# BEP2_rev1_multiCB_RPM.net
KiCad netlist of a schematic drawn in EAGLE
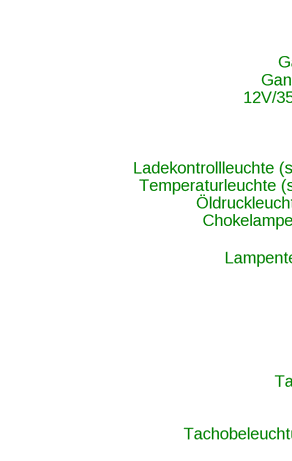
[diagram p0: schematic, sheet 1, part 1 of 2]
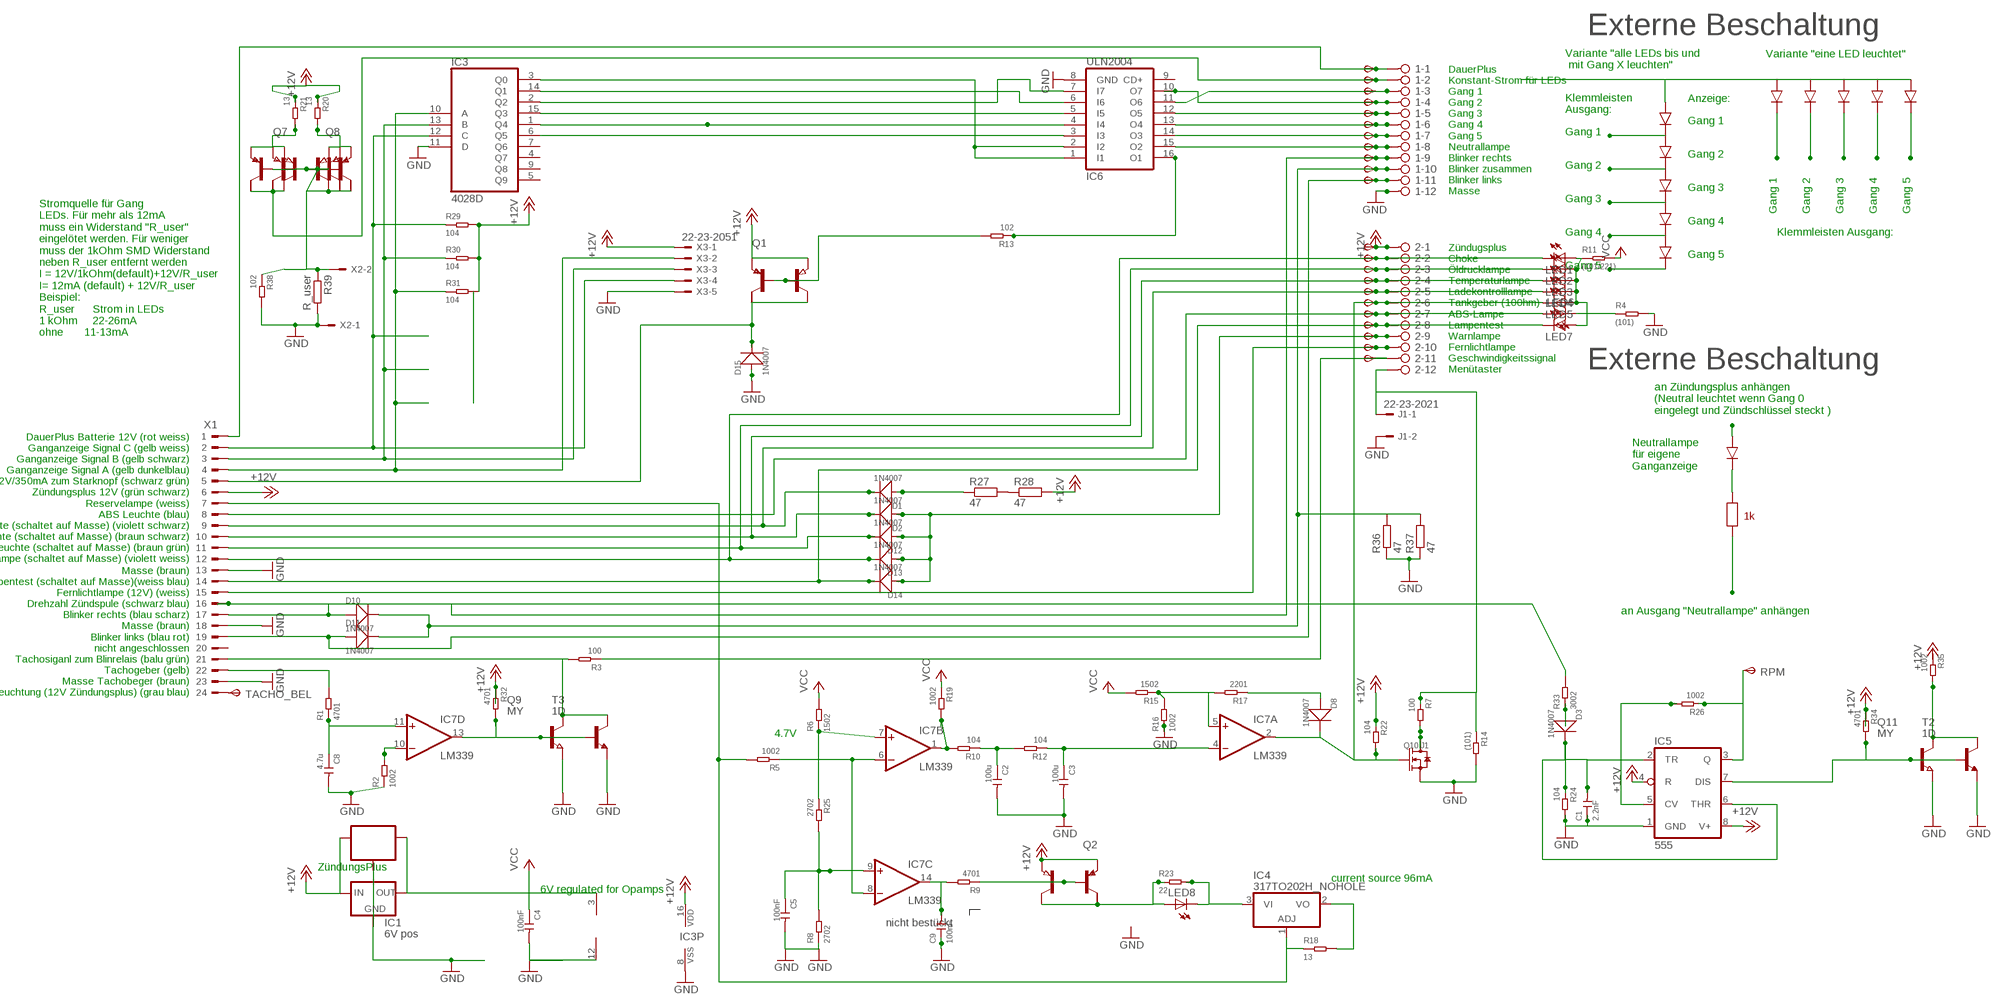
[diagram p1: schematic, sheet 1, part 2 of 2]

(export (version "E")
  (design (tool "Eeschema 10.0.6"))
  (components
    (comp (ref "1")
      (value "2081-1132")
      (footprint "eagle-import:12-PIN")
      (libsource (lib "eagle-import") (part "2081-1132"))
    )
    (comp (ref "2")
      (value "2081-1132")
      (footprint "eagle-import:12-PIN")
      (libsource (lib "eagle-import") (part "2081-1132"))
    )
    (comp (ref "C1")
      (value "2.2nF")
      (footprint "eagle-import:C0805")
      (fields (field (name "MPN") "CC0805KRX7R9BB104"))
      (libsource (lib "eagle-import") (part "CERAMIC-100NF-50V-10%-X7R(0805)"))
    )
    (comp (ref "C2")
      (value "100u")
      (footprint "eagle-import:C1206")
      (fields (field (name "MPN") "GRM31CR60J107ME39L"))
      (libsource (lib "eagle-import") (part "CERAMIC-100UF-6.3V-20%-X5R(1206)"))
    )
    (comp (ref "C3")
      (value "100u")
      (footprint "eagle-import:C1206")
      (fields (field (name "MPN") "GRM31CR60J107ME39L"))
      (libsource (lib "eagle-import") (part "CERAMIC-100UF-6.3V-20%-X5R(1206)"))
    )
    (comp (ref "C4")
      (value "100nF")
      (footprint "eagle-import:C0805")
      (fields (field (name "MPN") "CC0805KRX7R9BB104"))
      (libsource (lib "eagle-import") (part "CERAMIC-100NF-50V-10%-X7R(0805)"))
    )
    (comp (ref "C5")
      (value "100nF")
      (footprint "eagle-import:C0805")
      (fields (field (name "MPN") "CC0805KRX7R9BB104"))
      (libsource (lib "eagle-import") (part "CERAMIC-100NF-50V-10%-X7R(0805)"))
    )
    (comp (ref "C8")
      (value "4.7u")
      (footprint "eagle-import:C0805")
      (fields (field (name "MPN") "CC0805KKX5R8BB475"))
      (libsource (lib "eagle-import") (part "CERAMIC-4.7UF-25V-10%-X5R(0805)"))
    )
    (comp (ref "C9")
      (value "100nF")
      (footprint "eagle-import:C0805")
      (fields (field (name "MPN") "CC0805KRX7R9BB104"))
      (libsource (lib "eagle-import") (part "CERAMIC-100NF-50V-10%-X7R(0805)"))
    )
    (comp (ref "D1")
      (value "1N4007")
      (footprint "eagle-import:DO-214AC")
      (libsource (lib "eagle-import") (part "DIODE-GEN-PURPOSE-1KV-1A(DO-214AC)"))
    )
    (comp (ref "D2")
      (value "1N4007")
      (footprint "eagle-import:DO-214AC")
      (libsource (lib "eagle-import") (part "DIODE-GEN-PURPOSE-1KV-1A(DO-214AC)"))
    )
    (comp (ref "D3")
      (value "1N4007")
      (footprint "eagle-import:DO-214AC")
      (libsource (lib "eagle-import") (part "DIODE-GEN-PURPOSE-1KV-1A(DO-214AC)"))
    )
    (comp (ref "D8")
      (value "1N4007")
      (footprint "eagle-import:DO-214AC")
      (libsource (lib "eagle-import") (part "Seeed-Diode-2016_DIODE-GEN-PURPOSE-1KV-1A(DO-214AC)"))
    )
    (comp (ref "D10")
      (value "1N4007")
      (footprint "eagle-import:DO-214AC")
      (libsource (lib "eagle-import") (part "DIODE-GEN-PURPOSE-1KV-1A(DO-214AC)"))
    )
    (comp (ref "D11")
      (value "1N4007")
      (footprint "eagle-import:DO-214AC")
      (libsource (lib "eagle-import") (part "DIODE-GEN-PURPOSE-1KV-1A(DO-214AC)"))
    )
    (comp (ref "D12")
      (value "1N4007")
      (footprint "eagle-import:DO-214AC")
      (libsource (lib "eagle-import") (part "DIODE-GEN-PURPOSE-1KV-1A(DO-214AC)"))
    )
    (comp (ref "D13")
      (value "1N4007")
      (footprint "eagle-import:DO-214AC")
      (libsource (lib "eagle-import") (part "DIODE-GEN-PURPOSE-1KV-1A(DO-214AC)"))
    )
    (comp (ref "D14")
      (value "1N4007")
      (footprint "eagle-import:DO-214AC")
      (libsource (lib "eagle-import") (part "DIODE-GEN-PURPOSE-1KV-1A(DO-214AC)"))
    )
    (comp (ref "D15")
      (value "1N4007")
      (footprint "eagle-import:DO-214AC")
      (libsource (lib "eagle-import") (part "DIODE-GEN-PURPOSE-1KV-1A(DO-214AC)"))
    )
    (comp (ref "IC1")
      (value "6V pos")
      (footprint "eagle-import:78LXX")
      (libsource (lib "eagle-import") (part "v-reg_78LXX"))
    )
    (comp (ref "IC2")
      (value "78LXX-SOT89")
      (footprint "eagle-import:SOT89")
      (libsource (lib "eagle-import") (part "78LXX-SOT89"))
    )
    (comp (ref "IC3")
      (value "4028D")
      (footprint "eagle-import:SO16")
      (libsource (lib "eagle-import") (part "4028D"))
    )
    (comp (ref "IC4")
      (value "317TO202H_NOHOLE")
      (footprint "eagle-import:TO220H_NOHOLE")
      (libsource (lib "eagle-import") (part "317TO202H_NOHOLE"))
    )
    (comp (ref "IC5")
      (value "555")
      (footprint "eagle-import:SO08")
      (libsource (lib "eagle-import") (part "555DNE"))
    )
    (comp (ref "IC6")
      (value "ULN2004")
      (footprint "eagle-import:SO16")
      (libsource (lib "eagle-import") (part "ULN2004AD"))
    )
    (comp (ref "IC7")
      (value "LM339")
      (footprint "eagle-import:SO14")
      (libsource (lib "eagle-import") (part "LM339D"))
    )
    (comp (ref "J1")
      (value "22-23-2021")
      (footprint "eagle-import:22-23-2021")
      (fields (field (name "MF") "MOLEX"))
      (libsource (lib "eagle-import") (part "22-23-2021"))
    )
    (comp (ref "LED1")
      (value "LEDLD260")
      (footprint "eagle-import:LD260")
      (libsource (lib "eagle-import") (part "LEDLD260"))
    )
    (comp (ref "LED2")
      (value "LEDLD260")
      (footprint "eagle-import:LD260")
      (libsource (lib "eagle-import") (part "LEDLD260"))
    )
    (comp (ref "LED3")
      (value "LEDLD260")
      (footprint "eagle-import:LD260")
      (libsource (lib "eagle-import") (part "LEDLD260"))
    )
    (comp (ref "LED4")
      (value "LEDLD260")
      (footprint "eagle-import:LD260")
      (libsource (lib "eagle-import") (part "LEDLD260"))
    )
    (comp (ref "LED5")
      (value "LEDLD260")
      (footprint "eagle-import:LD260")
      (libsource (lib "eagle-import") (part "LEDLD260"))
    )
    (comp (ref "LED6")
      (value "LEDLD260")
      (footprint "eagle-import:LD260")
      (libsource (lib "eagle-import") (part "LEDLD260"))
    )
    (comp (ref "LED7")
      (value "LEDLD260")
      (footprint "eagle-import:LD260")
      (libsource (lib "eagle-import") (part "LEDLD260"))
    )
    (comp (ref "LED8")
      (value "LEDLD260")
      (footprint "eagle-import:LD260")
      (libsource (lib "eagle-import") (part "LEDLD260"))
    )
    (comp (ref "Q1")
      (value "PNP-TRANSISTOR_SOT89")
      (footprint "eagle-import:SOT89")
      (libsource (lib "eagle-import") (part "PNP-TRANSISTOR_SOT89"))
    )
    (comp (ref "Q2")
      (value "PNP-TRANSISTOR_SOT89")
      (footprint "eagle-import:SOT89")
      (libsource (lib "eagle-import") (part "PNP-TRANSISTOR_SOT89"))
    )
    (comp (ref "Q3")
      (value "AH-16")
      (footprint "eagle-import:SOT223")
      (libsource (lib "eagle-import") (part "BCP53T1"))
    )
    (comp (ref "Q4")
      (value "AH-16")
      (footprint "eagle-import:SOT223")
      (libsource (lib "eagle-import") (part "BCP53T1"))
    )
    (comp (ref "Q5")
      (value "(AH-16)")
      (footprint "eagle-import:SOT223")
      (libsource (lib "eagle-import") (part "BCP53T1"))
    )
    (comp (ref "Q6")
      (value "(AH-16)")
      (footprint "eagle-import:SOT223")
      (libsource (lib "eagle-import") (part "BCP53T1"))
    )
    (comp (ref "Q7")
      (value "PNP-TRANSISTOR_SOT89")
      (footprint "eagle-import:SOT89")
      (libsource (lib "eagle-import") (part "PNP-TRANSISTOR_SOT89"))
    )
    (comp (ref "Q8")
      (value "PNP-TRANSISTOR_SOT89")
      (footprint "eagle-import:SOT89")
      (libsource (lib "eagle-import") (part "PNP-TRANSISTOR_SOT89"))
    )
    (comp (ref "Q9")
      (value "MY")
      (footprint "eagle-import:SOT89")
      (libsource (lib "eagle-import") (part "NPN-TRANSISTOR_SOT89"))
    )
    (comp (ref "Q10")
      (value "J1")
      (footprint "eagle-import:SOT-23")
      (fields (field (name "MPN") "BSS138W-7-F"))
      (libsource (lib "eagle-import") (part "SMD-MOSFET-N-CH-50V-200MA-BSS138W-7-F(SOT-23)"))
    )
    (comp (ref "Q11")
      (value "MY")
      (footprint "eagle-import:SOT89")
      (libsource (lib "eagle-import") (part "NPN-TRANSISTOR_SOT89"))
    )
    (comp (ref "R1")
      (value "4701")
      (footprint "eagle-import:R0805")
      (fields (field (name "MPN") "RC0805JR-074K7L"))
      (libsource (lib "eagle-import") (part "SMD-RES-4.7K-5%-1/8W(0805)"))
    )
    (comp (ref "R2")
      (value "1002")
      (footprint "eagle-import:R0805")
      (fields (field (name "MPN") "RC0805FR-0710KL"))
      (libsource (lib "eagle-import") (part "SMD-RES-10K-1%-1/8W(0805)"))
    )
    (comp (ref "R3")
      (value "100")
      (footprint "eagle-import:R0805")
      (fields (field (name "MPN") "RC0805JR-07220RL"))
      (libsource (lib "eagle-import") (part "SMD-RES-220R-5%-1/8W(0805)"))
    )
    (comp (ref "R4")
      (value "(101)")
      (footprint "eagle-import:R0805")
      (fields (field (name "MPN") "RC0805JR-07100RL"))
      (libsource (lib "eagle-import") (part "SMD-RES-100R-5%-1/8W(0805)"))
    )
    (comp (ref "R5")
      (value "1002")
      (footprint "eagle-import:R0805")
      (fields (field (name "MPN") "RC0805FR-0710KL"))
      (libsource (lib "eagle-import") (part "SMD-RES-10K-1%-1/8W(0805)"))
    )
    (comp (ref "R6")
      (value "1502")
      (footprint "eagle-import:R0805")
      (fields (field (name "MPN") "RC0805FR-0710KL"))
      (libsource (lib "eagle-import") (part "SMD-RES-10K-1%-1/8W(0805)"))
    )
    (comp (ref "R7")
      (value "100")
      (footprint "eagle-import:R0805")
      (fields (field (name "MPN") "RC0805JR-072K2L"))
      (libsource (lib "eagle-import") (part "SMD-RES-2.2K-5%-1/8W(0805)"))
    )
    (comp (ref "R8")
      (value "2702")
      (footprint "eagle-import:R0805")
      (fields (field (name "MPN") "RC0805JR-074K7L"))
      (libsource (lib "eagle-import") (part "SMD-RES-4.7K-5%-1/8W(0805)"))
    )
    (comp (ref "R9")
      (value "4701")
      (footprint "eagle-import:R0805")
      (fields (field (name "MPN") "RC0805JR-074K7L"))
      (libsource (lib "eagle-import") (part "SMD-RES-4.7K-5%-1/8W(0805)"))
    )
    (comp (ref "R10")
      (value "104")
      (footprint "eagle-import:R0805")
      (fields (field (name "MPN") "RC0805FR-0710KL"))
      (libsource (lib "eagle-import") (part "SMD-RES-10K-1%-1/8W(0805)"))
    )
    (comp (ref "R11")
      (value "(101/221)")
      (footprint "eagle-import:R0805")
      (fields (field (name "MPN") "RC0805JR-07100RL"))
      (libsource (lib "eagle-import") (part "SMD-RES-100R-5%-1/8W(0805)"))
    )
    (comp (ref "R12")
      (value "104")
      (footprint "eagle-import:R0805")
      (fields (field (name "MPN") "RC0805FR-0710KL"))
      (libsource (lib "eagle-import") (part "SMD-RES-10K-1%-1/8W(0805)"))
    )
    (comp (ref "R13")
      (value "102")
      (footprint "eagle-import:R0805")
      (fields (field (name "MPN") "RC0805JR-071KL"))
      (libsource (lib "eagle-import") (part "SMD-RES-1K-5%-1/8W(0805)"))
    )
    (comp (ref "R14")
      (value "(101)")
      (footprint "eagle-import:R0805")
      (fields (field (name "MPN") "RC0805JR-072K2L"))
      (libsource (lib "eagle-import") (part "SMD-RES-2.2K-5%-1/8W(0805)"))
    )
    (comp (ref "R15")
      (value "1502")
      (footprint "eagle-import:R0805")
      (fields (field (name "MPN") "RC0805FR-0710KL"))
      (libsource (lib "eagle-import") (part "SMD-RES-10K-1%-1/8W(0805)"))
    )
    (comp (ref "R16")
      (value "1002")
      (footprint "eagle-import:R0805")
      (fields (field (name "MPN") "RC0805FR-0710KL"))
      (libsource (lib "eagle-import") (part "SMD-RES-10K-1%-1/8W(0805)"))
    )
    (comp (ref "R17")
      (value "2201")
      (footprint "eagle-import:R0805")
      (fields (field (name "MPN") "RC0805JR-072K2L"))
      (libsource (lib "eagle-import") (part "SMD-RES-2.2K-5%-1/8W(0805)"))
    )
    (comp (ref "R18")
      (value "13")
      (footprint "eagle-import:R1206")
      (fields (field (name "MPN") "RC1206JR-0713RL"))
      (libsource (lib "eagle-import") (part "SMD-RES-13R-5%-1/4W(1206)"))
    )
    (comp (ref "R19")
      (value "1002")
      (footprint "eagle-import:R0805")
      (fields (field (name "MPN") "RC0805FR-0710KL"))
      (libsource (lib "eagle-import") (part "SMD-RES-10K-1%-1/8W(0805)"))
    )
    (comp (ref "R20")
      (value "13")
      (footprint "eagle-import:R1206")
      (fields (field (name "MPN") "RC1206JR-0713RL"))
      (libsource (lib "eagle-import") (part "SMD-RES-13R-5%-1/4W(1206)"))
    )
    (comp (ref "R21")
      (value "13")
      (footprint "eagle-import:R1206")
      (fields (field (name "MPN") "RC1206JR-0713RL"))
      (libsource (lib "eagle-import") (part "SMD-RES-13R-5%-1/4W(1206)"))
    )
    (comp (ref "R22")
      (value "104")
      (footprint "eagle-import:R0805")
      (fields (field (name "MPN") "RC0805FR-0710KL"))
      (libsource (lib "eagle-import") (part "SMD-RES-10K-1%-1/8W(0805)"))
    )
    (comp (ref "R23")
      (value "22")
      (footprint "eagle-import:R1206")
      (fields (field (name "MPN") "RC1206JR-0713RL"))
      (libsource (lib "eagle-import") (part "SMD-RES-13R-5%-1/4W(1206)"))
    )
    (comp (ref "R24")
      (value "104")
      (footprint "eagle-import:R0805")
      (fields (field (name "MPN") "RC0805FR-0710KL"))
      (libsource (lib "eagle-import") (part "SMD-RES-10K-1%-1/8W(0805)"))
    )
    (comp (ref "R25")
      (value "2702")
      (footprint "eagle-import:R0805")
      (fields (field (name "MPN") "RC0805JR-074K7L"))
      (libsource (lib "eagle-import") (part "SMD-RES-4.7K-5%-1/8W(0805)"))
    )
    (comp (ref "R26")
      (value "1002")
      (footprint "eagle-import:R0805")
      (fields (field (name "MPN") "RC0805FR-0710KL"))
      (libsource (lib "eagle-import") (part "SMD-RES-10K-1%-1/8W(0805)"))
    )
    (comp (ref "R27")
      (value "47")
      (footprint "eagle-import:V235_17_1MM")
      (libsource (lib "eagle-import") (part "R-EU_V235/17_1MM"))
    )
    (comp (ref "R28")
      (value "47")
      (footprint "eagle-import:V235_17_1MM")
      (libsource (lib "eagle-import") (part "R-EU_V235/17_1MM"))
    )
    (comp (ref "R29")
      (value "104")
      (footprint "eagle-import:R0805")
      (fields (field (name "MPN") "RC0805FR-0710KL"))
      (libsource (lib "eagle-import") (part "SMD-RES-10K-1%-1/8W(0805)"))
    )
    (comp (ref "R30")
      (value "104")
      (footprint "eagle-import:R0805")
      (fields (field (name "MPN") "RC0805FR-0710KL"))
      (libsource (lib "eagle-import") (part "SMD-RES-10K-1%-1/8W(0805)"))
    )
    (comp (ref "R31")
      (value "104")
      (footprint "eagle-import:R0805")
      (fields (field (name "MPN") "RC0805FR-0710KL"))
      (libsource (lib "eagle-import") (part "SMD-RES-10K-1%-1/8W(0805)"))
    )
    (comp (ref "R32")
      (value "4701")
      (footprint "eagle-import:R0805")
      (fields (field (name "MPN") "RC0805JR-074K7L"))
      (libsource (lib "eagle-import") (part "SMD-RES-4.7K-5%-1/8W(0805)"))
    )
    (comp (ref "R33")
      (value "3002")
      (footprint "eagle-import:R0805")
      (fields (field (name "MPN") "RC0805FR-0710KL"))
      (libsource (lib "eagle-import") (part "SMD-RES-10K-1%-1/8W(0805)"))
    )
    (comp (ref "R34")
      (value "4701")
      (footprint "eagle-import:R0805")
      (fields (field (name "MPN") "RC0805JR-074K7L"))
      (libsource (lib "eagle-import") (part "SMD-RES-4.7K-5%-1/8W(0805)"))
    )
    (comp (ref "R35")
      (value "1002")
      (footprint "eagle-import:R0805")
      (fields (field (name "MPN") "RC0805JR-074K7L"))
      (libsource (lib "eagle-import") (part "SMD-RES-4.7K-5%-1/8W(0805)"))
    )
    (comp (ref "R36")
      (value "47")
      (footprint "eagle-import:V235_17_1MM")
      (libsource (lib "eagle-import") (part "R-EU_V235/17_1MM"))
    )
    (comp (ref "R37")
      (value "47")
      (footprint "eagle-import:V235_17_1MM")
      (libsource (lib "eagle-import") (part "R-EU_V235/17_1MM"))
    )
    (comp (ref "R38")
      (value "102")
      (footprint "eagle-import:R0805")
      (fields (field (name "MPN") "RC0805JR-071KL"))
      (libsource (lib "eagle-import") (part "SMD-RES-1K-5%-1/8W(0805)"))
    )
    (comp (ref "R39")
      (value "R_user")
      (footprint "eagle-import:R0805")
      (libsource (lib "eagle-import") (part "R-EU_R0805"))
    )
    (comp (ref "RPM")
      (value "TPSP1_1MM")
      (footprint "eagle-import:P1_1.0MM")
      (libsource (lib "eagle-import") (part "TPSP1_1MM"))
    )
    (comp (ref "T1")
      (value "PNP2SM8")
      (footprint "eagle-import:SM8")
      (libsource (lib "eagle-import") (part "PNP2SM8"))
    )
    (comp (ref "T2")
      (value "1D")
      (footprint "eagle-import:SOT23-BEC")
      (libsource (lib "eagle-import") (part "-NPN-SOT23-BECMMBTA42LT1"))
    )
    (comp (ref "T3")
      (value "1D")
      (footprint "eagle-import:SOT23-BEC")
      (libsource (lib "eagle-import") (part "-NPN-SOT23-BECMMBTA42LT1"))
    )
    (comp (ref "TACHO_BEL")
      (value "TPSP1_1MM")
      (footprint "eagle-import:P1_1.0MM")
      (libsource (lib "eagle-import") (part "TPSP1_1MM"))
    )
    (comp (ref "TP1")
      (value "TPSB1.8")
      (footprint "eagle-import:B1.8")
      (libsource (lib "eagle-import") (part "TPSB1.8"))
    )
    (comp (ref "TP2")
      (value "TPSB1.8")
      (footprint "eagle-import:B1.8")
      (libsource (lib "eagle-import") (part "TPSB1.8"))
    )
    (comp (ref "TP3")
      (value "TPSB1.8")
      (footprint "eagle-import:B1.8")
      (libsource (lib "eagle-import") (part "TPSB1.8"))
    )
    (comp (ref "TP4")
      (value "TPSB1.8")
      (footprint "eagle-import:B1.8")
      (libsource (lib "eagle-import") (part "TPSB1.8"))
    )
    (comp (ref "TP5")
      (value "TPSB1.8")
      (footprint "eagle-import:B1.8")
      (libsource (lib "eagle-import") (part "TPSB1.8"))
    )
    (comp (ref "TP6")
      (value "TPSB1.8")
      (footprint "eagle-import:B1.8")
      (libsource (lib "eagle-import") (part "TPSB1.8"))
    )
    (comp (ref "TP7")
      (value "TPSB1.8")
      (footprint "eagle-import:B1.8")
      (libsource (lib "eagle-import") (part "TPSB1.8"))
    )
    (comp (ref "TP8")
      (value "TPSB1.8")
      (footprint "eagle-import:B1.8")
      (libsource (lib "eagle-import") (part "TPSB1.8"))
    )
    (comp (ref "TP9")
      (value "TPSB1.8")
      (footprint "eagle-import:B1.8")
      (libsource (lib "eagle-import") (part "TPSB1.8"))
    )
    (comp (ref "TP10")
      (value "TPSB1.8")
      (footprint "eagle-import:B1.8")
      (libsource (lib "eagle-import") (part "TPSB1.8"))
    )
    (comp (ref "TP11")
      (value "TPSB1.8")
      (footprint "eagle-import:B1.8")
      (libsource (lib "eagle-import") (part "TPSB1.8"))
    )
    (comp (ref "TP12")
      (value "TPSB1.8")
      (footprint "eagle-import:B1.8")
      (libsource (lib "eagle-import") (part "TPSB1.8"))
    )
    (comp (ref "TP16")
      (value "TPSB1.8")
      (footprint "eagle-import:B1.8")
      (libsource (lib "eagle-import") (part "TPSB1.8"))
    )
    (comp (ref "TP17")
      (value "TPSB1.8")
      (footprint "eagle-import:B1.8")
      (libsource (lib "eagle-import") (part "TPSB1.8"))
    )
    (comp (ref "TP18")
      (value "TPSB1.8")
      (footprint "eagle-import:B1.8")
      (libsource (lib "eagle-import") (part "TPSB1.8"))
    )
    (comp (ref "TP19")
      (value "TPSB1.8")
      (footprint "eagle-import:B1.8")
      (libsource (lib "eagle-import") (part "TPSB1.8"))
    )
    (comp (ref "TP21")
      (value "TPSB1.8")
      (footprint "eagle-import:B1.8")
      (libsource (lib "eagle-import") (part "TPSB1.8"))
    )
    (comp (ref "TP22")
      (value "TPSB1.8")
      (footprint "eagle-import:B1.8")
      (libsource (lib "eagle-import") (part "TPSB1.8"))
    )
    (comp (ref "TP23")
      (value "TPSB1.8")
      (footprint "eagle-import:B1.8")
      (libsource (lib "eagle-import") (part "TPSB1.8"))
    )
    (comp (ref "TP24")
      (value "TPSB1,27")
      (footprint "eagle-import:B1,27")
      (libsource (lib "eagle-import") (part "TPSB1,27"))
    )
    (comp (ref "TP25")
      (value "TPSB1.8")
      (footprint "eagle-import:B1.8")
      (libsource (lib "eagle-import") (part "TPSB1.8"))
    )
    (comp (ref "TP26")
      (value "TPSB1.8")
      (footprint "eagle-import:B1.8")
      (libsource (lib "eagle-import") (part "TPSB1.8"))
    )
    (comp (ref "X1")
      (value "CON_BMWV2")
      (footprint "eagle-import:24-PIN_V2")
      (libsource (lib "eagle-import") (part "CON_BMWV2"))
    )
    (comp (ref "X2")
      (value "22-23-2021")
      (footprint "eagle-import:22-23-2021")
      (fields (field (name "MF") "MOLEX"))
      (libsource (lib "eagle-import") (part "22-23-2021"))
    )
    (comp (ref "X3")
      (value "22-23-2051")
      (footprint "eagle-import:22-23-2051")
      (fields (field (name "MF") "MOLEX"))
      (libsource (lib "eagle-import") (part "22-23-2051"))
    )
  )
  (nets
    (net (code "1") (name "+12V") (class "Default")
      (node (ref "2") (pin "1") (pinfunction "KL_1") (pintype "passive"))
      (node (ref "IC1") (pin "IN") (pinfunction "IN_IN") (pintype "input"))
      (node (ref "IC2") (pin "3") (pinfunction "IN_3") (pintype "input"))
      (node (ref "IC3") (pin "16") (pinfunction "VDD_16") (pintype "power_in"))
      (node (ref "IC5") (pin "4") (pinfunction "R_4") (pintype "input"))
      (node (ref "IC5") (pin "8") (pinfunction "V+_8") (pintype "power_in"))
      (node (ref "Q1") (pin "3") (pinfunction "E_3") (pintype "passive"))
      (node (ref "Q2") (pin "3") (pinfunction "E_3") (pintype "passive"))
      (node (ref "Q3") (pin "3") (pinfunction "E_3") (pintype "passive"))
      (node (ref "Q4") (pin "3") (pinfunction "E_3") (pintype "passive"))
      (node (ref "R20") (pin "1") (pinfunction "1_1") (pintype "passive"))
      (node (ref "R21") (pin "1") (pinfunction "1_1") (pintype "passive"))
      (node (ref "R22") (pin "1") (pinfunction "1_1") (pintype "passive"))
      (node (ref "R28") (pin "2") (pinfunction "2_2") (pintype "passive"))
      (node (ref "R29") (pin "2") (pinfunction "2_2") (pintype "passive"))
      (node (ref "R30") (pin "2") (pinfunction "2_2") (pintype "passive"))
      (node (ref "R31") (pin "2") (pinfunction "2_2") (pintype "passive"))
      (node (ref "R32") (pin "1") (pinfunction "1_1") (pintype "passive"))
      (node (ref "R34") (pin "1") (pinfunction "1_1") (pintype "passive"))
      (node (ref "TP12") (pin "TP") (pinfunction "PP_TP") (pintype "input"))
      (node (ref "X1") (pin "6") (pinfunction "6_6") (pintype "passive"))
      (node (ref "X3") (pin "1") (pinfunction "S_1") (pintype "passive"))
    )
    (net (code "2") (name "GND") (class "Default")
      (node (ref "1") (pin "12") (pinfunction "KL_12") (pintype "passive"))
      (node (ref "C1") (pin "1") (pinfunction "1_1") (pintype "passive"))
      (node (ref "C2") (pin "2") (pinfunction "2_2") (pintype "passive"))
      (node (ref "C3") (pin "2") (pinfunction "2_2") (pintype "passive"))
      (node (ref "C4") (pin "2") (pinfunction "2_2") (pintype "passive"))
      (node (ref "C5") (pin "2") (pinfunction "2_2") (pintype "passive"))
      (node (ref "C8") (pin "2") (pinfunction "2_2") (pintype "passive"))
      (node (ref "C9") (pin "1") (pinfunction "1_1") (pintype "passive"))
      (node (ref "D15") (pin "1") (pinfunction "+_1") (pintype "passive"))
      (node (ref "IC1") (pin "GND") (pinfunction "GND_GND") (pintype "input"))
      (node (ref "IC2") (pin "2") (pinfunction "GND_2") (pintype "input"))
      (node (ref "IC2") (pin "4") (pinfunction "GND_4") (pintype "input"))
      (node (ref "IC3") (pin "11") (pinfunction "D_11") (pintype "input"))
      (node (ref "IC3") (pin "8") (pinfunction "VSS_8") (pintype "power_in"))
      (node (ref "IC5") (pin "1") (pinfunction "GND_1") (pintype "power_in"))
      (node (ref "IC6") (pin "8") (pinfunction "GND_8") (pintype "power_in"))
      (node (ref "IC7") (pin "12") (pinfunction "GND_12") (pintype "power_in"))
      (node (ref "J1") (pin "2") (pinfunction "S_2") (pintype "passive"))
      (node (ref "Q10") (pin "2") (pinfunction "S_2") (pintype "passive"))
      (node (ref "Q11") (pin "3") (pinfunction "E_3") (pintype "passive"))
      (node (ref "Q9") (pin "3") (pinfunction "E_3") (pintype "passive"))
      (node (ref "R14") (pin "2") (pinfunction "2_2") (pintype "passive"))
      (node (ref "R16") (pin "1") (pinfunction "1_1") (pintype "passive"))
      (node (ref "R2") (pin "1") (pinfunction "1_1") (pintype "passive"))
      (node (ref "R24") (pin "2") (pinfunction "2_2") (pintype "passive"))
      (node (ref "R36") (pin "1") (pinfunction "1_1") (pintype "passive"))
      (node (ref "R37") (pin "1") (pinfunction "1_1") (pintype "passive"))
      (node (ref "R38") (pin "2") (pinfunction "2_2") (pintype "passive"))
      (node (ref "R39") (pin "2") (pinfunction "2_2") (pintype "passive"))
      (node (ref "R4") (pin "2") (pinfunction "2_2") (pintype "passive"))
      (node (ref "R8") (pin "1") (pinfunction "1_1") (pintype "passive"))
      (node (ref "T2") (pin "E") (pinfunction "E_E") (pintype "passive"))
      (node (ref "T3") (pin "E") (pinfunction "E_E") (pintype "passive"))
      (node (ref "X1") (pin "13") (pinfunction "13_13") (pintype "passive"))
      (node (ref "X1") (pin "18") (pinfunction "18_18") (pintype "passive"))
      (node (ref "X1") (pin "23") (pinfunction "23_23") (pintype "passive"))
      (node (ref "X2") (pin "1") (pinfunction "S_1") (pintype "passive"))
      (node (ref "X3") (pin "5") (pinfunction "S_5") (pintype "passive"))
    )
    (net (code "3") (name "Net-(1A-KL)") (class "Default")
      (node (ref "1") (pin "1") (pinfunction "KL_1") (pintype "passive"))
      (node (ref "TP1") (pin "TP") (pinfunction "PP_TP") (pintype "input"))
      (node (ref "X1") (pin "1") (pinfunction "1_1") (pintype "passive"))
    )
    (net (code "4") (name "Net-(1B-KL)") (class "Default")
      (node (ref "1") (pin "10") (pinfunction "KL_10") (pintype "passive"))
      (node (ref "D10") (pin "2") (pinfunction "-_2") (pintype "passive"))
      (node (ref "D11") (pin "2") (pinfunction "-_2") (pintype "passive"))
      (node (ref "R36") (pin "2") (pinfunction "2_2") (pintype "passive"))
      (node (ref "R37") (pin "2") (pinfunction "2_2") (pintype "passive"))
      (node (ref "TP10") (pin "TP") (pinfunction "PP_TP") (pintype "input"))
    )
    (net (code "5") (name "Net-(1C-KL)") (class "Default")
      (node (ref "1") (pin "11") (pinfunction "KL_11") (pintype "passive"))
      (node (ref "D11") (pin "1") (pinfunction "+_1") (pintype "passive"))
      (node (ref "TP11") (pin "TP") (pinfunction "PP_TP") (pintype "input"))
      (node (ref "X1") (pin "19") (pinfunction "19_19") (pintype "passive"))
    )
    (net (code "6") (name "Net-(1E-KL)") (class "Default")
      (node (ref "1") (pin "2") (pinfunction "KL_2") (pintype "passive"))
      (node (ref "Q5") (pin "2") (pinfunction "C_2") (pintype "passive"))
      (node (ref "Q8") (pin "2") (pinfunction "C_2") (pintype "passive"))
      (node (ref "T1") (pin "8") (pinfunction "C1_8") (pintype "passive"))
      (node (ref "TP2") (pin "TP") (pinfunction "PP_TP") (pintype "input"))
    )
    (net (code "7") (name "Net-(1F-KL)") (class "Default")
      (node (ref "1") (pin "3") (pinfunction "KL_3") (pintype "passive"))
      (node (ref "IC6") (pin "11") (pinfunction "O6_11") (pintype "open_collector"))
      (node (ref "TP3") (pin "TP") (pinfunction "PP_TP") (pintype "input"))
    )
    (net (code "8") (name "Net-(1G-KL)") (class "Default")
      (node (ref "1") (pin "4") (pinfunction "KL_4") (pintype "passive"))
      (node (ref "IC6") (pin "10") (pinfunction "O7_10") (pintype "open_collector"))
      (node (ref "TP4") (pin "TP") (pinfunction "PP_TP") (pintype "input"))
    )
    (net (code "9") (name "Net-(1H-KL)") (class "Default")
      (node (ref "1") (pin "5") (pinfunction "KL_5") (pintype "passive"))
      (node (ref "IC6") (pin "12") (pinfunction "O5_12") (pintype "open_collector"))
      (node (ref "TP5") (pin "TP") (pinfunction "PP_TP") (pintype "input"))
    )
    (net (code "10") (name "Net-(1I-KL)") (class "Default")
      (node (ref "1") (pin "6") (pinfunction "KL_6") (pintype "passive"))
      (node (ref "IC6") (pin "13") (pinfunction "O4_13") (pintype "open_collector"))
      (node (ref "TP6") (pin "TP") (pinfunction "PP_TP") (pintype "input"))
    )
    (net (code "11") (name "Net-(1J-KL)") (class "Default")
      (node (ref "1") (pin "7") (pinfunction "KL_7") (pintype "passive"))
      (node (ref "IC6") (pin "14") (pinfunction "O3_14") (pintype "open_collector"))
      (node (ref "TP7") (pin "TP") (pinfunction "PP_TP") (pintype "input"))
    )
    (net (code "12") (name "Net-(1K-KL)") (class "Default")
      (node (ref "1") (pin "8") (pinfunction "KL_8") (pintype "passive"))
      (node (ref "IC6") (pin "15") (pinfunction "O2_15") (pintype "open_collector"))
      (node (ref "TP8") (pin "TP") (pinfunction "PP_TP") (pintype "input"))
    )
    (net (code "13") (name "Net-(1L-KL)") (class "Default")
      (node (ref "1") (pin "9") (pinfunction "KL_9") (pintype "passive"))
      (node (ref "D10") (pin "1") (pinfunction "+_1") (pintype "passive"))
      (node (ref "TP9") (pin "TP") (pinfunction "PP_TP") (pintype "input"))
      (node (ref "X1") (pin "17") (pinfunction "17_17") (pintype "passive"))
    )
    (net (code "14") (name "Net-(2B-KL)") (class "Default")
      (node (ref "2") (pin "10") (pinfunction "KL_10") (pintype "passive"))
      (node (ref "TP25") (pin "TP") (pinfunction "PP_TP") (pintype "input"))
      (node (ref "X1") (pin "15") (pinfunction "15_15") (pintype "passive"))
    )
    (net (code "15") (name "Net-(2C-KL)") (class "Default")
      (node (ref "2") (pin "11") (pinfunction "KL_11") (pintype "passive"))
      (node (ref "R3") (pin "1") (pinfunction "1_1") (pintype "passive"))
      (node (ref "TP26") (pin "TP") (pinfunction "PP_TP") (pintype "input"))
    )
    (net (code "16") (name "Net-(2D-KL)") (class "Default")
      (node (ref "2") (pin "12") (pinfunction "KL_12") (pintype "passive"))
      (node (ref "J1") (pin "1") (pinfunction "S_1") (pintype "passive"))
      (node (ref "R14") (pin "1") (pinfunction "1_1") (pintype "passive"))
      (node (ref "R7") (pin "1") (pinfunction "1_1") (pintype "passive"))
    )
    (net (code "17") (name "Net-(2E-KL)") (class "Default")
      (node (ref "2") (pin "2") (pinfunction "KL_2") (pintype "passive"))
      (node (ref "D13") (pin "2") (pinfunction "-_2") (pintype "passive"))
      (node (ref "LED1") (pin "K") (pinfunction "C_K") (pintype "passive"))
      (node (ref "TP16") (pin "TP") (pinfunction "PP_TP") (pintype "input"))
      (node (ref "X1") (pin "12") (pinfunction "12_12") (pintype "passive"))
    )
    (net (code "18") (name "Net-(2F-KL)") (class "Default")
      (node (ref "2") (pin "3") (pinfunction "KL_3") (pintype "passive"))
      (node (ref "D12") (pin "2") (pinfunction "-_2") (pintype "passive"))
      (node (ref "LED2") (pin "K") (pinfunction "C_K") (pintype "passive"))
      (node (ref "TP17") (pin "TP") (pinfunction "PP_TP") (pintype "input"))
      (node (ref "X1") (pin "11") (pinfunction "11_11") (pintype "passive"))
    )
    (net (code "19") (name "Net-(2G-KL)") (class "Default")
      (node (ref "2") (pin "4") (pinfunction "KL_4") (pintype "passive"))
      (node (ref "D2") (pin "2") (pinfunction "-_2") (pintype "passive"))
      (node (ref "LED3") (pin "K") (pinfunction "C_K") (pintype "passive"))
      (node (ref "TP18") (pin "TP") (pinfunction "PP_TP") (pintype "input"))
      (node (ref "X1") (pin "10") (pinfunction "10_10") (pintype "passive"))
    )
    (net (code "20") (name "Net-(2H-KL)") (class "Default")
      (node (ref "2") (pin "5") (pinfunction "KL_5") (pintype "passive"))
      (node (ref "D1") (pin "2") (pinfunction "-_2") (pintype "passive"))
      (node (ref "LED4") (pin "K") (pinfunction "C_K") (pintype "passive"))
      (node (ref "TP19") (pin "TP") (pinfunction "PP_TP") (pintype "input"))
      (node (ref "X1") (pin "9") (pinfunction "9_9") (pintype "passive"))
    )
    (net (code "21") (name "Net-(2I-KL)") (class "Default")
      (node (ref "2") (pin "6") (pinfunction "KL_6") (pintype "passive"))
      (node (ref "D8") (pin "2") (pinfunction "-_2") (pintype "passive"))
      (node (ref "IC7") (pin "2") (pinfunction "OUT_2") (pintype "open_collector"))
      (node (ref "LED5") (pin "K") (pinfunction "C_K") (pintype "passive"))
      (node (ref "Q10") (pin "1") (pinfunction "G_1") (pintype "passive"))
      (node (ref "R22") (pin "2") (pinfunction "2_2") (pintype "passive"))
      (node (ref "TP21") (pin "TP") (pinfunction "PP_TP") (pintype "input"))
    )
    (net (code "22") (name "Net-(2J-KL)") (class "Default")
      (node (ref "2") (pin "7") (pinfunction "KL_7") (pintype "passive"))
      (node (ref "LED6") (pin "A") (pinfunction "A_A") (pintype "passive"))
      (node (ref "TP22") (pin "TP") (pinfunction "PP_TP") (pintype "input"))
      (node (ref "X1") (pin "8") (pinfunction "8_8") (pintype "passive"))
    )
    (net (code "23") (name "Net-(2K-KL)") (class "Default")
      (node (ref "2") (pin "8") (pinfunction "KL_8") (pintype "passive"))
      (node (ref "D14") (pin "2") (pinfunction "-_2") (pintype "passive"))
      (node (ref "LED7") (pin "K") (pinfunction "C_K") (pintype "passive"))
      (node (ref "TP23") (pin "TP") (pinfunction "PP_TP") (pintype "input"))
      (node (ref "X1") (pin "14") (pinfunction "14_14") (pintype "passive"))
    )
    (net (code "24") (name "Net-(2L-KL)") (class "Default")
      (node (ref "2") (pin "9") (pinfunction "KL_9") (pintype "passive"))
      (node (ref "D12") (pin "1") (pinfunction "+_1") (pintype "passive"))
      (node (ref "D13") (pin "1") (pinfunction "+_1") (pintype "passive"))
      (node (ref "D14") (pin "1") (pinfunction "+_1") (pintype "passive"))
      (node (ref "D2") (pin "1") (pinfunction "+_1") (pintype "passive"))
      (node (ref "TP24") (pin "TP") (pinfunction "PP_TP") (pintype "input"))
    )
    (net (code "25") (name "Net-(C2-Pad1)") (class "Default")
      (node (ref "C2") (pin "1") (pinfunction "1_1") (pintype "passive"))
      (node (ref "R10") (pin "1") (pinfunction "1_1") (pintype "passive"))
      (node (ref "R12") (pin "2") (pinfunction "2_2") (pintype "passive"))
    )
    (net (code "26") (name "Net-(D1-+)") (class "Default")
      (node (ref "D1") (pin "1") (pinfunction "+_1") (pintype "passive"))
      (node (ref "R27") (pin "1") (pinfunction "1_1") (pintype "passive"))
    )
    (net (code "27") (name "Net-(D3-+)") (class "Default")
      (node (ref "D3") (pin "1") (pinfunction "+_1") (pintype "passive"))
      (node (ref "R33") (pin "1") (pinfunction "1_1") (pintype "passive"))
    )
    (net (code "28") (name "Net-(D3--)") (class "Default")
      (node (ref "C1") (pin "2") (pinfunction "2_2") (pintype "passive"))
      (node (ref "D3") (pin "2") (pinfunction "-_2") (pintype "passive"))
      (node (ref "IC5") (pin "2") (pinfunction "TR_2") (pintype "input"))
      (node (ref "IC5") (pin "6") (pinfunction "THR_6") (pintype "input"))
      (node (ref "R24") (pin "1") (pinfunction "1_1") (pintype "passive"))
    )
    (net (code "29") (name "Net-(D8-+)") (class "Default")
      (node (ref "D8") (pin "1") (pinfunction "+_1") (pintype "passive"))
      (node (ref "R17") (pin "1") (pinfunction "1_1") (pintype "passive"))
    )
    (net (code "30") (name "Net-(D15--)") (class "Default")
      (node (ref "D15") (pin "2") (pinfunction "-_2") (pintype "passive"))
      (node (ref "Q1") (pin "2") (pinfunction "C_2") (pintype "passive"))
      (node (ref "Q3") (pin "2") (pinfunction "C_2") (pintype "passive"))
      (node (ref "X1") (pin "5") (pinfunction "5_5") (pintype "passive"))
    )
    (net (code "31") (name "Net-(IC3A-A)") (class "Default")
      (node (ref "IC3") (pin "10") (pinfunction "A_10") (pintype "input"))
      (node (ref "R31") (pin "1") (pinfunction "1_1") (pintype "passive"))
      (node (ref "X1") (pin "4") (pinfunction "4_4") (pintype "passive"))
      (node (ref "X3") (pin "2") (pinfunction "S_2") (pintype "passive"))
    )
    (net (code "32") (name "Net-(IC3A-B)") (class "Default")
      (node (ref "IC3") (pin "13") (pinfunction "B_13") (pintype "input"))
      (node (ref "R30") (pin "1") (pinfunction "1_1") (pintype "passive"))
      (node (ref "X1") (pin "3") (pinfunction "3_3") (pintype "passive"))
      (node (ref "X3") (pin "3") (pinfunction "S_3") (pintype "passive"))
    )
    (net (code "33") (name "Net-(IC3A-C)") (class "Default")
      (node (ref "IC3") (pin "12") (pinfunction "C_12") (pintype "input"))
      (node (ref "R29") (pin "1") (pinfunction "1_1") (pintype "passive"))
      (node (ref "X1") (pin "2") (pinfunction "2_2") (pintype "passive"))
      (node (ref "X3") (pin "4") (pinfunction "S_4") (pintype "passive"))
    )
    (net (code "34") (name "Net-(IC3A-Q0)") (class "Default")
      (node (ref "IC3") (pin "3") (pinfunction "Q0_3") (pintype "output"))
      (node (ref "IC6") (pin "1") (pinfunction "I1_1") (pintype "input"))
      (node (ref "IC6") (pin "2") (pinfunction "I2_2") (pintype "input"))
    )
    (net (code "35") (name "Net-(IC3A-Q1)") (class "Default")
      (node (ref "IC3") (pin "14") (pinfunction "Q1_14") (pintype "output"))
      (node (ref "IC6") (pin "6") (pinfunction "I6_6") (pintype "input"))
    )
    (net (code "36") (name "Net-(IC3A-Q2)") (class "Default")
      (node (ref "IC3") (pin "2") (pinfunction "Q2_2") (pintype "output"))
      (node (ref "IC6") (pin "7") (pinfunction "I7_7") (pintype "input"))
    )
    (net (code "37") (name "Net-(IC3A-Q3)") (class "Default")
      (node (ref "IC3") (pin "15") (pinfunction "Q3_15") (pintype "output"))
      (node (ref "IC6") (pin "5") (pinfunction "I5_5") (pintype "input"))
    )
    (net (code "38") (name "Net-(IC3A-Q4)") (class "Default")
      (node (ref "IC3") (pin "1") (pinfunction "Q4_1") (pintype "output"))
      (node (ref "IC6") (pin "4") (pinfunction "I4_4") (pintype "input"))
    )
    (net (code "39") (name "Net-(IC3A-Q5)") (class "Default")
      (node (ref "IC3") (pin "6") (pinfunction "Q5_6") (pintype "output"))
      (node (ref "IC6") (pin "3") (pinfunction "I3_3") (pintype "input"))
    )
    (net (code "40") (name "Net-(IC4-ADJ)") (class "Default")
      (node (ref "IC4") (pin "1") (pinfunction "ADJ_1") (pintype "input"))
      (node (ref "R18") (pin "1") (pinfunction "1_1") (pintype "passive"))
      (node (ref "R5") (pin "2") (pinfunction "2_2") (pintype "passive"))
      (node (ref "X1") (pin "7") (pinfunction "7_7") (pintype "passive"))
    )
    (net (code "41") (name "Net-(IC4-VI)") (class "Default")
      (node (ref "IC4") (pin "3") (pinfunction "VI_3") (pintype "input"))
      (node (ref "LED8") (pin "K") (pinfunction "C_K") (pintype "passive"))
      (node (ref "R23") (pin "2") (pinfunction "2_2") (pintype "passive"))
    )
    (net (code "42") (name "Net-(IC4-VO)") (class "Default")
      (node (ref "IC4") (pin "2") (pinfunction "VO_2") (pintype "passive"))
      (node (ref "R18") (pin "2") (pinfunction "2_2") (pintype "passive"))
    )
    (net (code "43") (name "Net-(IC5-CV)") (class "Default")
      (node (ref "IC5") (pin "5") (pinfunction "CV_5") (pintype "input"))
      (node (ref "R26") (pin "2") (pinfunction "2_2") (pintype "passive"))
    )
    (net (code "44") (name "Net-(IC5-DIS)") (class "Default")
      (node (ref "IC5") (pin "7") (pinfunction "DIS_7") (pintype "input"))
      (node (ref "Q11") (pin "1") (pinfunction "B_1") (pintype "passive"))
      (node (ref "R34") (pin "2") (pinfunction "2_2") (pintype "passive"))
      (node (ref "T2") (pin "B") (pinfunction "B_B") (pintype "passive"))
    )
    (net (code "45") (name "Net-(IC5-Q)") (class "Default")
      (node (ref "IC5") (pin "3") (pinfunction "Q_3") (pintype "output"))
      (node (ref "R26") (pin "1") (pinfunction "1_1") (pintype "passive"))
      (node (ref "RPM") (pin "TP") (pinfunction "PP_TP") (pintype "input"))
    )
    (net (code "46") (name "Net-(IC6-O1)") (class "Default")
      (node (ref "IC6") (pin "16") (pinfunction "O1_16") (pintype "open_collector"))
      (node (ref "R13") (pin "1") (pinfunction "1_1") (pintype "passive"))
    )
    (net (code "47") (name "Net-(IC7A-+IN)") (class "Default")
      (node (ref "IC7") (pin "5") (pinfunction "+IN_5") (pintype "input"))
      (node (ref "R15") (pin "1") (pinfunction "1_1") (pintype "passive"))
      (node (ref "R16") (pin "2") (pinfunction "2_2") (pintype "passive"))
      (node (ref "R17") (pin "2") (pinfunction "2_2") (pintype "passive"))
    )
    (net (code "48") (name "Net-(IC7A--IN)") (class "Default")
      (node (ref "C3") (pin "1") (pinfunction "1_1") (pintype "passive"))
      (node (ref "IC7") (pin "4") (pinfunction "-IN_4") (pintype "input"))
      (node (ref "R12") (pin "1") (pinfunction "1_1") (pintype "passive"))
    )
    (net (code "49") (name "Net-(IC7B-+IN)") (class "Default")
      (node (ref "IC7") (pin "7") (pinfunction "+IN_7") (pintype "input"))
      (node (ref "R25") (pin "1") (pinfunction "1_1") (pintype "passive"))
      (node (ref "R6") (pin "1") (pinfunction "1_1") (pintype "passive"))
    )
    (net (code "50") (name "Net-(IC7B--IN)") (class "Default")
      (node (ref "IC7") (pin "6") (pinfunction "-IN_6") (pintype "input"))
      (node (ref "IC7") (pin "8") (pinfunction "-IN_8") (pintype "input"))
      (node (ref "R5") (pin "1") (pinfunction "1_1") (pintype "passive"))
    )
    (net (code "51") (name "Net-(IC7B-OUT)") (class "Default")
      (node (ref "IC7") (pin "1") (pinfunction "OUT_1") (pintype "open_collector"))
      (node (ref "R10") (pin "2") (pinfunction "2_2") (pintype "passive"))
      (node (ref "R19") (pin "2") (pinfunction "2_2") (pintype "passive"))
    )
    (net (code "52") (name "Net-(IC7C-+IN)") (class "Default")
      (node (ref "C5") (pin "1") (pinfunction "1_1") (pintype "passive"))
      (node (ref "IC7") (pin "9") (pinfunction "+IN_9") (pintype "input"))
      (node (ref "R25") (pin "2") (pinfunction "2_2") (pintype "passive"))
      (node (ref "R8") (pin "2") (pinfunction "2_2") (pintype "passive"))
    )
    (net (code "53") (name "Net-(IC7C-OUT)") (class "Default")
      (node (ref "C9") (pin "2") (pinfunction "2_2") (pintype "passive"))
      (node (ref "IC7") (pin "14") (pinfunction "OUT_14") (pintype "open_collector"))
      (node (ref "R9") (pin "2") (pinfunction "2_2") (pintype "passive"))
    )
    (net (code "54") (name "Net-(IC7D-+IN)") (class "Default")
      (node (ref "C8") (pin "1") (pinfunction "1_1") (pintype "passive"))
      (node (ref "IC7") (pin "11") (pinfunction "+IN_11") (pintype "input"))
      (node (ref "R1") (pin "1") (pinfunction "1_1") (pintype "passive"))
    )
    (net (code "55") (name "Net-(IC7D--IN)") (class "Default")
      (node (ref "IC7") (pin "10") (pinfunction "-IN_10") (pintype "input"))
      (node (ref "R2") (pin "2") (pinfunction "2_2") (pintype "passive"))
    )
    (net (code "56") (name "Net-(IC7D-OUT)") (class "Default")
      (node (ref "IC7") (pin "13") (pinfunction "OUT_13") (pintype "open_collector"))
      (node (ref "Q9") (pin "1") (pinfunction "B_1") (pintype "passive"))
      (node (ref "R32") (pin "2") (pinfunction "2_2") (pintype "passive"))
      (node (ref "T3") (pin "B") (pinfunction "B_B") (pintype "passive"))
    )
    (net (code "57") (name "Net-(LED1-PadA)") (class "Default")
      (node (ref "LED1") (pin "A") (pinfunction "A_A") (pintype "passive"))
      (node (ref "LED2") (pin "A") (pinfunction "A_A") (pintype "passive"))
      (node (ref "LED3") (pin "A") (pinfunction "A_A") (pintype "passive"))
      (node (ref "LED4") (pin "A") (pinfunction "A_A") (pintype "passive"))
      (node (ref "LED5") (pin "A") (pinfunction "A_A") (pintype "passive"))
      (node (ref "LED7") (pin "A") (pinfunction "A_A") (pintype "passive"))
      (node (ref "R11") (pin "1") (pinfunction "1_1") (pintype "passive"))
    )
    (net (code "58") (name "Net-(LED6-C)") (class "Default")
      (node (ref "LED6") (pin "K") (pinfunction "C_K") (pintype "passive"))
      (node (ref "R4") (pin "1") (pinfunction "1_1") (pintype "passive"))
    )
    (net (code "59") (name "Net-(Q1-B)") (class "Default")
      (node (ref "Q1") (pin "1") (pinfunction "B_1") (pintype "passive"))
      (node (ref "Q3") (pin "1") (pinfunction "B_1") (pintype "passive"))
      (node (ref "R13") (pin "2") (pinfunction "2_2") (pintype "passive"))
    )
    (net (code "60") (name "Net-(Q2-B)") (class "Default")
      (node (ref "Q2") (pin "1") (pinfunction "B_1") (pintype "passive"))
      (node (ref "Q4") (pin "1") (pinfunction "B_1") (pintype "passive"))
      (node (ref "R9") (pin "1") (pinfunction "1_1") (pintype "passive"))
    )
    (net (code "61") (name "Net-(Q2-C)") (class "Default")
      (node (ref "LED8") (pin "A") (pinfunction "A_A") (pintype "passive"))
      (node (ref "Q2") (pin "2") (pinfunction "C_2") (pintype "passive"))
      (node (ref "Q4") (pin "2") (pinfunction "C_2") (pintype "passive"))
      (node (ref "R23") (pin "1") (pinfunction "1_1") (pintype "passive"))
    )
    (net (code "62") (name "Net-(Q5-B)") (class "Default")
      (node (ref "Q5") (pin "1") (pinfunction "B_1") (pintype "passive"))
      (node (ref "Q6") (pin "1") (pinfunction "B_1") (pintype "passive"))
      (node (ref "Q6") (pin "2") (pinfunction "C_2") (pintype "passive"))
      (node (ref "Q7") (pin "1") (pinfunction "B_1") (pintype "passive"))
      (node (ref "Q7") (pin "2") (pinfunction "C_2") (pintype "passive"))
      (node (ref "Q8") (pin "1") (pinfunction "B_1") (pintype "passive"))
      (node (ref "R38") (pin "1") (pinfunction "1_1") (pintype "passive"))
      (node (ref "R39") (pin "1") (pinfunction "1_1") (pintype "passive"))
      (node (ref "T1") (pin "2") (pinfunction "B_2") (pintype "passive"))
      (node (ref "T1") (pin "4") (pinfunction "B_4") (pintype "passive"))
      (node (ref "T1") (pin "6") (pinfunction "C1_6") (pintype "passive"))
      (node (ref "X2") (pin "2") (pinfunction "S_2") (pintype "passive"))
    )
    (net (code "63") (name "Net-(Q5-E)") (class "Default")
      (node (ref "Q5") (pin "3") (pinfunction "E_3") (pintype "passive"))
      (node (ref "Q8") (pin "3") (pinfunction "E_3") (pintype "passive"))
      (node (ref "R21") (pin "2") (pinfunction "2_2") (pintype "passive"))
      (node (ref "T1") (pin "1") (pinfunction "E_1") (pintype "passive"))
    )
    (net (code "64") (name "Net-(Q6-E)") (class "Default")
      (node (ref "Q6") (pin "3") (pinfunction "E_3") (pintype "passive"))
      (node (ref "Q7") (pin "3") (pinfunction "E_3") (pintype "passive"))
      (node (ref "R20") (pin "2") (pinfunction "2_2") (pintype "passive"))
      (node (ref "T1") (pin "3") (pinfunction "E_3") (pintype "passive"))
    )
    (net (code "65") (name "Net-(Q9-C)") (class "Default")
      (node (ref "Q9") (pin "2") (pinfunction "C_2") (pintype "passive"))
      (node (ref "R3") (pin "2") (pinfunction "2_2") (pintype "passive"))
      (node (ref "T3") (pin "C") (pinfunction "C_C") (pintype "passive"))
      (node (ref "X1") (pin "21") (pinfunction "21_21") (pintype "passive"))
    )
    (net (code "66") (name "Net-(Q10-D)") (class "Default")
      (node (ref "Q10") (pin "3") (pinfunction "D_3") (pintype "passive"))
      (node (ref "R7") (pin "2") (pinfunction "2_2") (pintype "passive"))
    )
    (net (code "67") (name "Net-(Q11-C)") (class "Default")
      (node (ref "Q11") (pin "2") (pinfunction "C_2") (pintype "passive"))
      (node (ref "R35") (pin "2") (pinfunction "2_2") (pintype "passive"))
      (node (ref "T2") (pin "C") (pinfunction "C_C") (pintype "passive"))
    )
    (net (code "68") (name "Net-(R1-Pad2)") (class "Default")
      (node (ref "R1") (pin "2") (pinfunction "2_2") (pintype "passive"))
      (node (ref "X1") (pin "22") (pinfunction "22_22") (pintype "passive"))
    )
    (net (code "69") (name "Net-(R27-Pad2)") (class "Default")
      (node (ref "R27") (pin "2") (pinfunction "2_2") (pintype "passive"))
      (node (ref "R28") (pin "1") (pinfunction "1_1") (pintype "passive"))
    )
    (net (code "70") (name "Net-(R33-Pad2)") (class "Default")
      (node (ref "R33") (pin "2") (pinfunction "2_2") (pintype "passive"))
      (node (ref "X1") (pin "16") (pinfunction "16_16") (pintype "passive"))
    )
    (net (code "71") (name "Net-(TACHO_BEL-PP)") (class "Default")
      (node (ref "TACHO_BEL") (pin "TP") (pinfunction "PP_TP") (pintype "input"))
      (node (ref "X1") (pin "24") (pinfunction "24_24") (pintype "passive"))
    )
    (net (code "72") (name "VCC") (class "Default")
      (node (ref "C4") (pin "1") (pinfunction "1_1") (pintype "passive"))
      (node (ref "IC1") (pin "OUT") (pinfunction "OUT_OUT") (pintype "passive"))
      (node (ref "IC2") (pin "1") (pinfunction "OUT_1") (pintype "passive"))
      (node (ref "IC7") (pin "3") (pinfunction "V+_3") (pintype "power_in"))
      (node (ref "R11") (pin "2") (pinfunction "2_2") (pintype "passive"))
      (node (ref "R15") (pin "2") (pinfunction "2_2") (pintype "passive"))
      (node (ref "R19") (pin "1") (pinfunction "1_1") (pintype "passive"))
      (node (ref "R6") (pin "2") (pinfunction "2_2") (pintype "passive"))
    )
    (net (code "73") (name "unconnected-(IC3A-Q6-Pad7)") (class "Default")
      (node (ref "IC3") (pin "7") (pinfunction "Q6_7") (pintype "output"))
    )
    (net (code "74") (name "unconnected-(IC3A-Q7-Pad4)") (class "Default")
      (node (ref "IC3") (pin "4") (pinfunction "Q7_4") (pintype "output"))
    )
    (net (code "75") (name "unconnected-(IC3A-Q8-Pad9)") (class "Default")
      (node (ref "IC3") (pin "9") (pinfunction "Q8_9") (pintype "output"))
    )
    (net (code "76") (name "unconnected-(IC3A-Q9-Pad5)") (class "Default")
      (node (ref "IC3") (pin "5") (pinfunction "Q9_5") (pintype "output"))
    )
    (net (code "77") (name "unconnected-(IC6-CD+-Pad9)") (class "Default")
      (node (ref "IC6") (pin "9") (pinfunction "CD+_9") (pintype "passive"))
    )
    (net (code "78") (name "unconnected-(Q3-C{slash}-Pad4)") (class "Default")
      (node (ref "Q3") (pin "4") (pinfunction "C/_4") (pintype "passive"))
    )
    (net (code "79") (name "unconnected-(Q4-C{slash}-Pad4)") (class "Default")
      (node (ref "Q4") (pin "4") (pinfunction "C/_4") (pintype "passive"))
    )
    (net (code "80") (name "unconnected-(Q5-C{slash}-Pad4)") (class "Default")
      (node (ref "Q5") (pin "4") (pinfunction "C/_4") (pintype "passive"))
    )
    (net (code "81") (name "unconnected-(Q6-C{slash}-Pad4)") (class "Default")
      (node (ref "Q6") (pin "4") (pinfunction "C/_4") (pintype "passive"))
    )
    (net (code "82") (name "unconnected-(R35-Pad1)") (class "Default")
      (node (ref "R35") (pin "1") (pinfunction "1_1") (pintype "passive"))
    )
    (net (code "83") (name "unconnected-(T1A-C-Pad5)") (class "Default")
      (node (ref "T1") (pin "5") (pinfunction "C_5") (pintype "passive"))
    )
    (net (code "84") (name "unconnected-(T1B-C-Pad7)") (class "Default")
      (node (ref "T1") (pin "7") (pinfunction "C_7") (pintype "passive"))
    )
    (net (code "85") (name "unconnected-(X1-Pad20)") (class "Default")
      (node (ref "X1") (pin "20") (pinfunction "20_20") (pintype "passive"))
    )
  )
)
